# RPi_Extension_dac.net
KiCad netlist of a schematic drawn in EAGLE
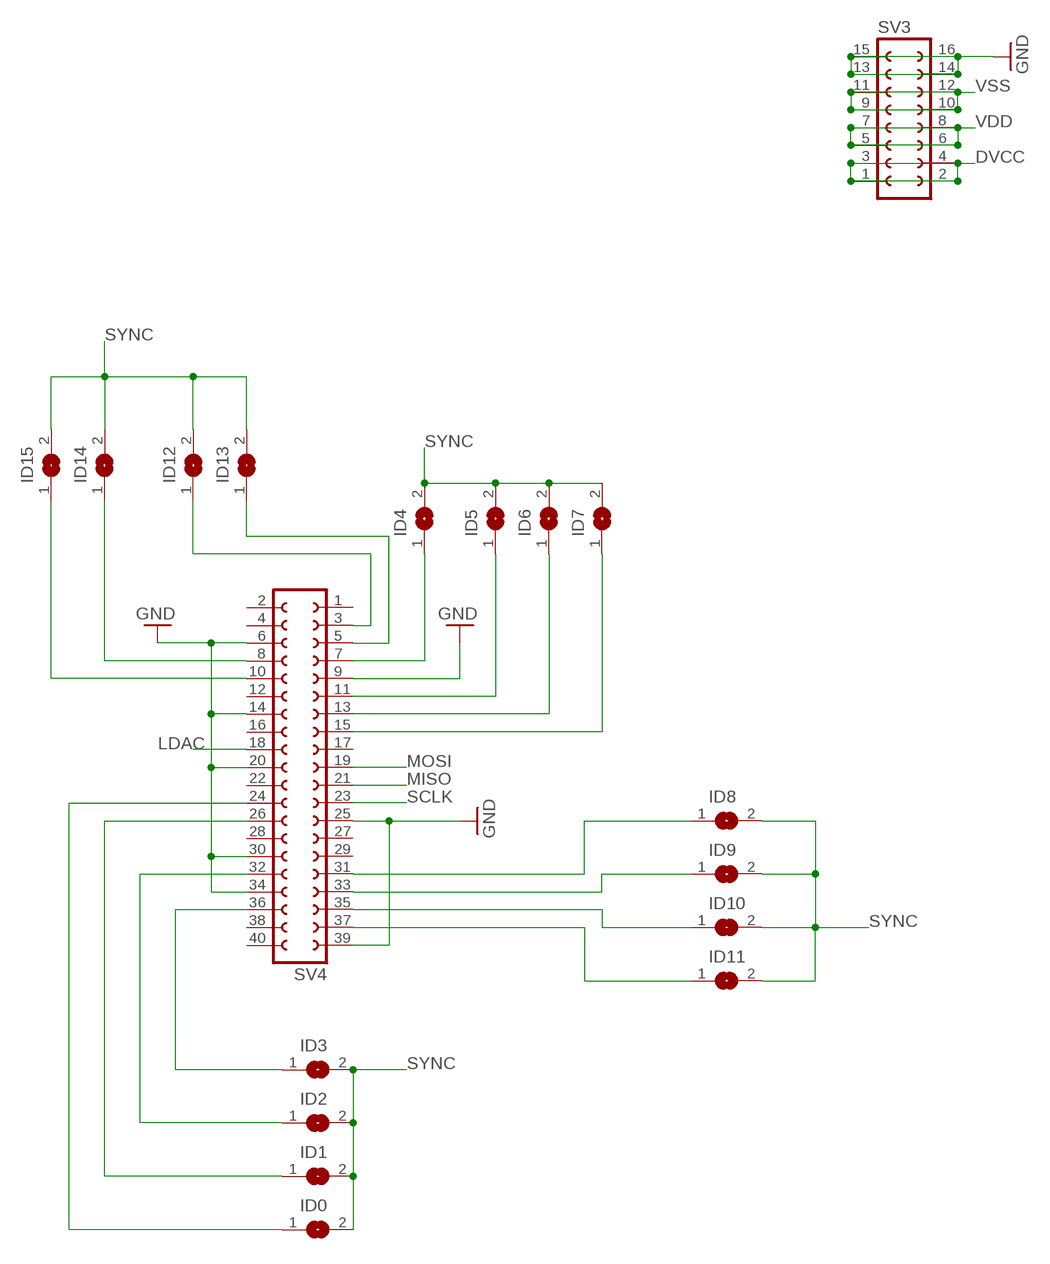
[diagram p0: schematic, sheet 1, part 1 of 2]
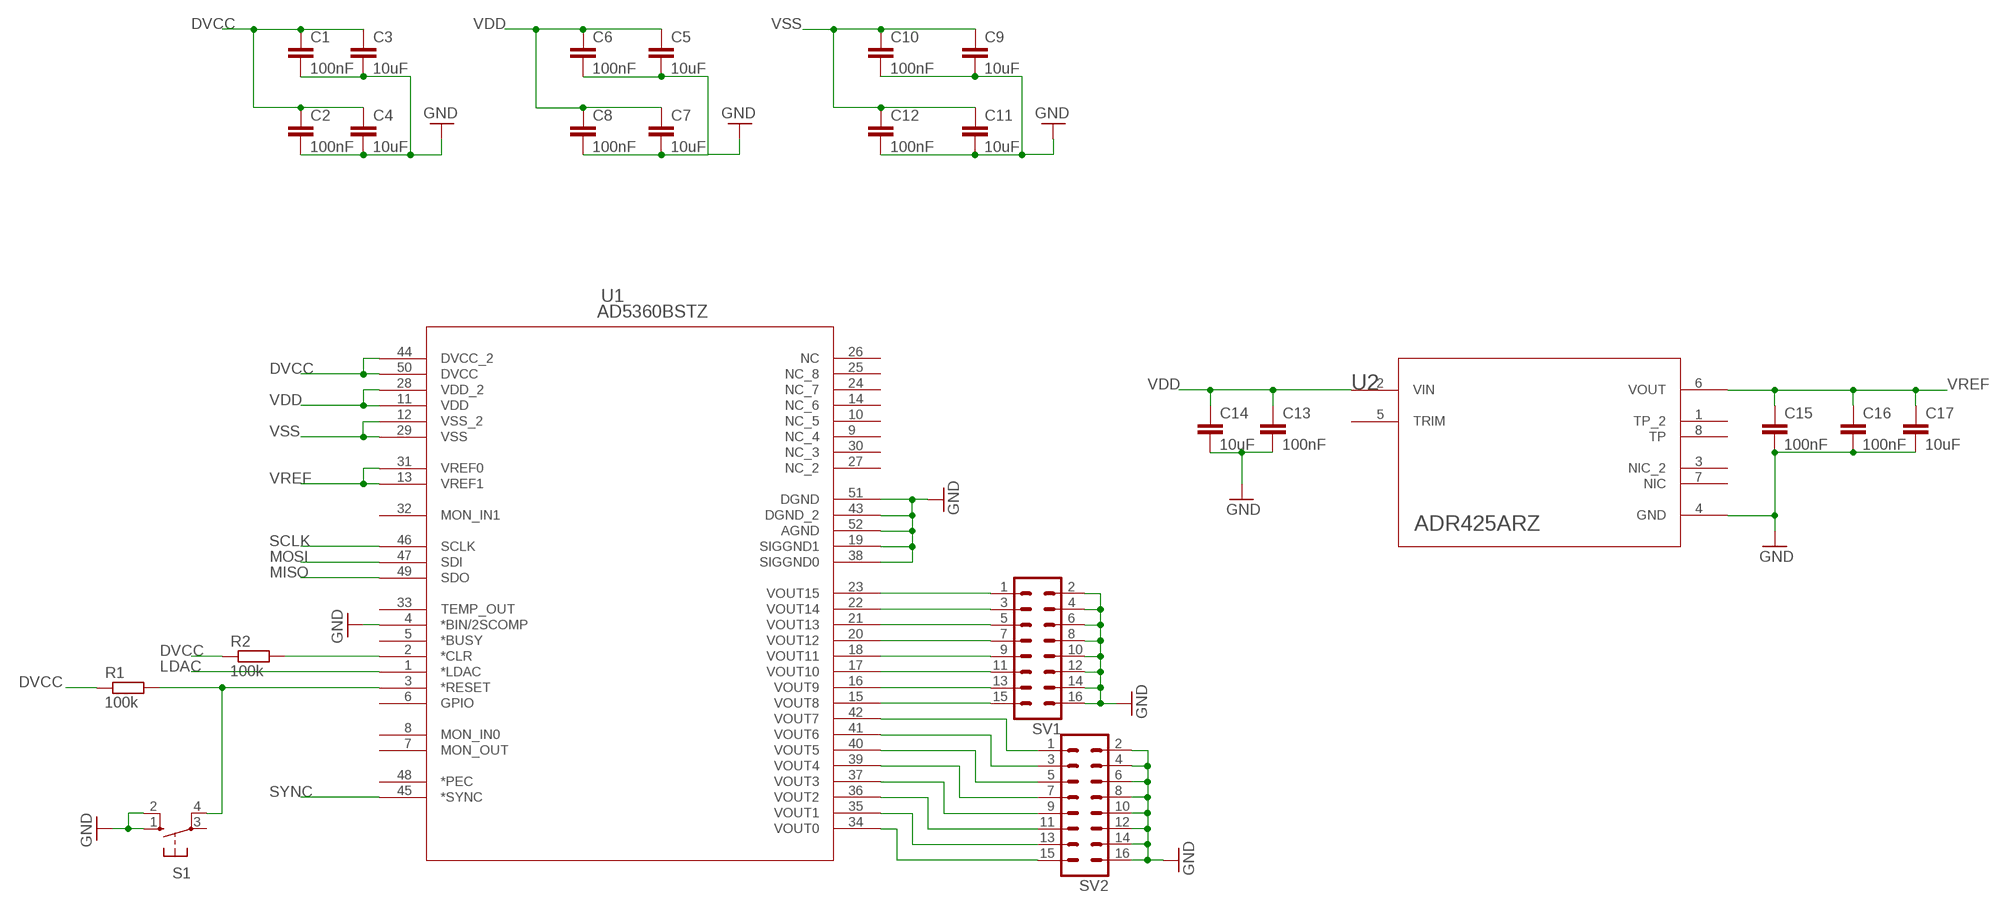
[diagram p1: schematic, sheet 1, part 2 of 2]

(export (version "E")
  (design (tool "Eeschema 10.0.6"))
  (components
    (comp (ref "C1")
      (value "100nF")
      (footprint "eagle-import:C0603")
      (libsource (lib "eagle-import") (part "C-EUC0603"))
    )
    (comp (ref "C2")
      (value "100nF")
      (footprint "eagle-import:C0603")
      (libsource (lib "eagle-import") (part "C-EUC0603"))
    )
    (comp (ref "C3")
      (value "10uF")
      (footprint "eagle-import:C1206")
      (libsource (lib "eagle-import") (part "C-EUC1206"))
    )
    (comp (ref "C4")
      (value "10uF")
      (footprint "eagle-import:C1206")
      (libsource (lib "eagle-import") (part "C-EUC1206"))
    )
    (comp (ref "C5")
      (value "10uF")
      (footprint "eagle-import:C1206")
      (libsource (lib "eagle-import") (part "C-EUC1206"))
    )
    (comp (ref "C6")
      (value "100nF")
      (footprint "eagle-import:C0603")
      (libsource (lib "eagle-import") (part "C-EUC0603"))
    )
    (comp (ref "C7")
      (value "10uF")
      (footprint "eagle-import:C1206")
      (libsource (lib "eagle-import") (part "C-EUC1206"))
    )
    (comp (ref "C8")
      (value "100nF")
      (footprint "eagle-import:C0603")
      (libsource (lib "eagle-import") (part "C-EUC0603"))
    )
    (comp (ref "C9")
      (value "10uF")
      (footprint "eagle-import:C1206")
      (libsource (lib "eagle-import") (part "C-EUC1206"))
    )
    (comp (ref "C10")
      (value "100nF")
      (footprint "eagle-import:C0603")
      (libsource (lib "eagle-import") (part "C-EUC0603"))
    )
    (comp (ref "C11")
      (value "10uF")
      (footprint "eagle-import:C1206")
      (libsource (lib "eagle-import") (part "C-EUC1206"))
    )
    (comp (ref "C12")
      (value "100nF")
      (footprint "eagle-import:C0603")
      (libsource (lib "eagle-import") (part "C-EUC0603"))
    )
    (comp (ref "C13")
      (value "100nF")
      (footprint "eagle-import:C0603")
      (libsource (lib "eagle-import") (part "C-EUC0603"))
    )
    (comp (ref "C14")
      (value "10uF")
      (footprint "eagle-import:C1206")
      (libsource (lib "eagle-import") (part "C-EUC1206"))
    )
    (comp (ref "C15")
      (value "100nF")
      (footprint "eagle-import:C0603")
      (libsource (lib "eagle-import") (part "C-EUC0603"))
    )
    (comp (ref "C16")
      (value "100nF")
      (footprint "eagle-import:C0603")
      (libsource (lib "eagle-import") (part "C-EUC0603"))
    )
    (comp (ref "C17")
      (value "10uF")
      (footprint "eagle-import:C1206")
      (libsource (lib "eagle-import") (part "C-EUC1206"))
    )
    (comp (ref "ID0") (value "SJ") (footprint "eagle-import:SJ") (libsource (lib "eagle-import") (part "SJ")))
    (comp (ref "ID1") (value "SJ") (footprint "eagle-import:SJ") (libsource (lib "eagle-import") (part "SJ")))
    (comp (ref "ID2") (value "SJ") (footprint "eagle-import:SJ") (libsource (lib "eagle-import") (part "SJ")))
    (comp (ref "ID3") (value "SJ") (footprint "eagle-import:SJ") (libsource (lib "eagle-import") (part "SJ")))
    (comp (ref "ID4") (value "SJ") (footprint "eagle-import:SJ") (libsource (lib "eagle-import") (part "SJ")))
    (comp (ref "ID5") (value "SJ") (footprint "eagle-import:SJ") (libsource (lib "eagle-import") (part "SJ")))
    (comp (ref "ID6") (value "SJ") (footprint "eagle-import:SJ") (libsource (lib "eagle-import") (part "SJ")))
    (comp (ref "ID7") (value "SJ") (footprint "eagle-import:SJ") (libsource (lib "eagle-import") (part "SJ")))
    (comp (ref "ID8") (value "SJ") (footprint "eagle-import:SJ") (libsource (lib "eagle-import") (part "SJ")))
    (comp (ref "ID9") (value "SJ") (footprint "eagle-import:SJ") (libsource (lib "eagle-import") (part "SJ")))
    (comp (ref "ID10")
      (value "SJ")
      (footprint "eagle-import:SJ")
      (libsource (lib "eagle-import") (part "SJ"))
    )
    (comp (ref "ID11")
      (value "SJ")
      (footprint "eagle-import:SJ")
      (libsource (lib "eagle-import") (part "SJ"))
    )
    (comp (ref "ID12")
      (value "SJ")
      (footprint "eagle-import:SJ")
      (libsource (lib "eagle-import") (part "SJ"))
    )
    (comp (ref "ID13")
      (value "SJ")
      (footprint "eagle-import:SJ")
      (libsource (lib "eagle-import") (part "SJ"))
    )
    (comp (ref "ID14")
      (value "SJ")
      (footprint "eagle-import:SJ")
      (libsource (lib "eagle-import") (part "SJ"))
    )
    (comp (ref "ID15")
      (value "SJ")
      (footprint "eagle-import:SJ")
      (libsource (lib "eagle-import") (part "SJ"))
    )
    (comp (ref "R1")
      (value "100k")
      (footprint "eagle-import:R0603")
      (libsource (lib "eagle-import") (part "R-EU_R0603"))
    )
    (comp (ref "R2")
      (value "100k")
      (footprint "eagle-import:R0603")
      (libsource (lib "eagle-import") (part "R-EU_R0603"))
    )
    (comp (ref "S1")
      (value "10-XX")
      (footprint "eagle-import:B3F-10XX")
      (fields (field (name "MPN") "B3F-1000"))
      (libsource (lib "eagle-import") (part "10-XX"))
    )
    (comp (ref "SV1")
      (value "MA08-2W")
      (footprint "eagle-import:MA08-2W")
      (libsource (lib "eagle-import") (part "MA08-2W"))
    )
    (comp (ref "SV2")
      (value "MA08-2W")
      (footprint "eagle-import:MA08-2W")
      (libsource (lib "eagle-import") (part "MA08-2W"))
    )
    (comp (ref "SV3")
      (value "FE08-2")
      (footprint "eagle-import:FE08-2")
      (libsource (lib "eagle-import") (part "FE08-2"))
    )
    (comp (ref "SV4")
      (value "FE20-2")
      (footprint "eagle-import:FE20-2")
      (libsource (lib "eagle-import") (part "FE20-2"))
    )
    (comp (ref "U1")
      (value "AD5360BSTZ")
      (footprint "eagle-import:ST_52")
      (libsource (lib "eagle-import") (part "AD5360BSTZ"))
    )
    (comp (ref "U2")
      (value "ADR425ARZ")
      (footprint "eagle-import:R_8")
      (fields (field (name "MANUFACTURER_PART_NUMBER") "ADR423ARZ"))
      (libsource (lib "eagle-import") (part "ADR423ARZ"))
    )
  )
  (nets
    (net (code "1") (name "/DVCC") (class "Default")
      (node (ref "C1") (pin "1") (pinfunction "1_1") (pintype "passive"))
      (node (ref "C2") (pin "1") (pinfunction "1_1") (pintype "passive"))
      (node (ref "C3") (pin "1") (pinfunction "1_1") (pintype "passive"))
      (node (ref "C4") (pin "1") (pinfunction "1_1") (pintype "passive"))
      (node (ref "R1") (pin "1") (pinfunction "1_1") (pintype "passive"))
      (node (ref "R2") (pin "1") (pinfunction "1_1") (pintype "passive"))
      (node (ref "SV3") (pin "1") (pinfunction "1_1") (pintype "passive"))
      (node (ref "SV3") (pin "2") (pinfunction "2_2") (pintype "passive"))
      (node (ref "SV3") (pin "3") (pinfunction "3_3") (pintype "passive"))
      (node (ref "SV3") (pin "4") (pinfunction "4_4") (pintype "passive"))
      (node (ref "U1") (pin "44") (pinfunction "DVCC_2_44") (pintype "passive"))
      (node (ref "U1") (pin "50") (pinfunction "DVCC_50") (pintype "passive"))
    )
    (net (code "2") (name "/LDAC") (class "Default")
      (node (ref "SV4") (pin "18") (pinfunction "18_18") (pintype "passive"))
      (node (ref "U1") (pin "1") (pinfunction "*LDAC_1") (pintype "passive"))
    )
    (net (code "3") (name "/MISO") (class "Default")
      (node (ref "SV4") (pin "21") (pinfunction "21_21") (pintype "passive"))
      (node (ref "U1") (pin "49") (pinfunction "SDO_49") (pintype "passive"))
    )
    (net (code "4") (name "/MOSI") (class "Default")
      (node (ref "SV4") (pin "19") (pinfunction "19_19") (pintype "passive"))
      (node (ref "U1") (pin "47") (pinfunction "SDI_47") (pintype "passive"))
    )
    (net (code "5") (name "/SCLK") (class "Default")
      (node (ref "SV4") (pin "23") (pinfunction "23_23") (pintype "passive"))
      (node (ref "U1") (pin "46") (pinfunction "SCLK_46") (pintype "passive"))
    )
    (net (code "6") (name "/SYNC") (class "Default")
      (node (ref "ID0") (pin "2") (pinfunction "2_2") (pintype "passive"))
      (node (ref "ID1") (pin "2") (pinfunction "2_2") (pintype "passive"))
      (node (ref "ID10") (pin "2") (pinfunction "2_2") (pintype "passive"))
      (node (ref "ID11") (pin "2") (pinfunction "2_2") (pintype "passive"))
      (node (ref "ID12") (pin "2") (pinfunction "2_2") (pintype "passive"))
      (node (ref "ID13") (pin "2") (pinfunction "2_2") (pintype "passive"))
      (node (ref "ID14") (pin "2") (pinfunction "2_2") (pintype "passive"))
      (node (ref "ID15") (pin "2") (pinfunction "2_2") (pintype "passive"))
      (node (ref "ID2") (pin "2") (pinfunction "2_2") (pintype "passive"))
      (node (ref "ID3") (pin "2") (pinfunction "2_2") (pintype "passive"))
      (node (ref "ID4") (pin "2") (pinfunction "2_2") (pintype "passive"))
      (node (ref "ID5") (pin "2") (pinfunction "2_2") (pintype "passive"))
      (node (ref "ID6") (pin "2") (pinfunction "2_2") (pintype "passive"))
      (node (ref "ID7") (pin "2") (pinfunction "2_2") (pintype "passive"))
      (node (ref "ID8") (pin "2") (pinfunction "2_2") (pintype "passive"))
      (node (ref "ID9") (pin "2") (pinfunction "2_2") (pintype "passive"))
      (node (ref "U1") (pin "45") (pinfunction "*SYNC_45") (pintype "passive"))
    )
    (net (code "7") (name "/VDD") (class "Default")
      (node (ref "C13") (pin "1") (pinfunction "1_1") (pintype "passive"))
      (node (ref "C14") (pin "1") (pinfunction "1_1") (pintype "passive"))
      (node (ref "C5") (pin "1") (pinfunction "1_1") (pintype "passive"))
      (node (ref "C6") (pin "1") (pinfunction "1_1") (pintype "passive"))
      (node (ref "C7") (pin "1") (pinfunction "1_1") (pintype "passive"))
      (node (ref "C8") (pin "1") (pinfunction "1_1") (pintype "passive"))
      (node (ref "SV3") (pin "5") (pinfunction "5_5") (pintype "passive"))
      (node (ref "SV3") (pin "6") (pinfunction "6_6") (pintype "passive"))
      (node (ref "SV3") (pin "7") (pinfunction "7_7") (pintype "passive"))
      (node (ref "SV3") (pin "8") (pinfunction "8_8") (pintype "passive"))
      (node (ref "U1") (pin "11") (pinfunction "VDD_11") (pintype "passive"))
      (node (ref "U1") (pin "28") (pinfunction "VDD_2_28") (pintype "passive"))
      (node (ref "U2") (pin "2") (pinfunction "VIN_2") (pintype "passive"))
    )
    (net (code "8") (name "/VREF") (class "Default")
      (node (ref "C15") (pin "1") (pinfunction "1_1") (pintype "passive"))
      (node (ref "C16") (pin "1") (pinfunction "1_1") (pintype "passive"))
      (node (ref "C17") (pin "1") (pinfunction "1_1") (pintype "passive"))
      (node (ref "U1") (pin "13") (pinfunction "VREF1_13") (pintype "passive"))
      (node (ref "U1") (pin "31") (pinfunction "VREF0_31") (pintype "passive"))
      (node (ref "U2") (pin "6") (pinfunction "VOUT_6") (pintype "passive"))
    )
    (net (code "9") (name "/VSS") (class "Default")
      (node (ref "C10") (pin "1") (pinfunction "1_1") (pintype "passive"))
      (node (ref "C11") (pin "1") (pinfunction "1_1") (pintype "passive"))
      (node (ref "C12") (pin "1") (pinfunction "1_1") (pintype "passive"))
      (node (ref "C9") (pin "1") (pinfunction "1_1") (pintype "passive"))
      (node (ref "SV3") (pin "10") (pinfunction "10_10") (pintype "passive"))
      (node (ref "SV3") (pin "11") (pinfunction "11_11") (pintype "passive"))
      (node (ref "SV3") (pin "12") (pinfunction "12_12") (pintype "passive"))
      (node (ref "SV3") (pin "9") (pinfunction "9_9") (pintype "passive"))
      (node (ref "U1") (pin "12") (pinfunction "VSS_2_12") (pintype "passive"))
      (node (ref "U1") (pin "29") (pinfunction "VSS_29") (pintype "passive"))
    )
    (net (code "10") (name "GND") (class "Default")
      (node (ref "C1") (pin "2") (pinfunction "2_2") (pintype "passive"))
      (node (ref "C10") (pin "2") (pinfunction "2_2") (pintype "passive"))
      (node (ref "C11") (pin "2") (pinfunction "2_2") (pintype "passive"))
      (node (ref "C12") (pin "2") (pinfunction "2_2") (pintype "passive"))
      (node (ref "C13") (pin "2") (pinfunction "2_2") (pintype "passive"))
      (node (ref "C14") (pin "2") (pinfunction "2_2") (pintype "passive"))
      (node (ref "C15") (pin "2") (pinfunction "2_2") (pintype "passive"))
      (node (ref "C16") (pin "2") (pinfunction "2_2") (pintype "passive"))
      (node (ref "C17") (pin "2") (pinfunction "2_2") (pintype "passive"))
      (node (ref "C2") (pin "2") (pinfunction "2_2") (pintype "passive"))
      (node (ref "C3") (pin "2") (pinfunction "2_2") (pintype "passive"))
      (node (ref "C4") (pin "2") (pinfunction "2_2") (pintype "passive"))
      (node (ref "C5") (pin "2") (pinfunction "2_2") (pintype "passive"))
      (node (ref "C6") (pin "2") (pinfunction "2_2") (pintype "passive"))
      (node (ref "C7") (pin "2") (pinfunction "2_2") (pintype "passive"))
      (node (ref "C8") (pin "2") (pinfunction "2_2") (pintype "passive"))
      (node (ref "C9") (pin "2") (pinfunction "2_2") (pintype "passive"))
      (node (ref "S1") (pin "1") (pinfunction "S_1") (pintype "passive"))
      (node (ref "S1") (pin "2") (pinfunction "S1_2") (pintype "passive"))
      (node (ref "SV1") (pin "10") (pinfunction "10_10") (pintype "passive"))
      (node (ref "SV1") (pin "12") (pinfunction "12_12") (pintype "passive"))
      (node (ref "SV1") (pin "14") (pinfunction "14_14") (pintype "passive"))
      (node (ref "SV1") (pin "16") (pinfunction "16_16") (pintype "passive"))
      (node (ref "SV1") (pin "2") (pinfunction "2_2") (pintype "passive"))
      (node (ref "SV1") (pin "4") (pinfunction "4_4") (pintype "passive"))
      (node (ref "SV1") (pin "6") (pinfunction "6_6") (pintype "passive"))
      (node (ref "SV1") (pin "8") (pinfunction "8_8") (pintype "passive"))
      (node (ref "SV2") (pin "10") (pinfunction "10_10") (pintype "passive"))
      (node (ref "SV2") (pin "12") (pinfunction "12_12") (pintype "passive"))
      (node (ref "SV2") (pin "14") (pinfunction "14_14") (pintype "passive"))
      (node (ref "SV2") (pin "16") (pinfunction "16_16") (pintype "passive"))
      (node (ref "SV2") (pin "2") (pinfunction "2_2") (pintype "passive"))
      (node (ref "SV2") (pin "4") (pinfunction "4_4") (pintype "passive"))
      (node (ref "SV2") (pin "6") (pinfunction "6_6") (pintype "passive"))
      (node (ref "SV2") (pin "8") (pinfunction "8_8") (pintype "passive"))
      (node (ref "SV3") (pin "13") (pinfunction "13_13") (pintype "passive"))
      (node (ref "SV3") (pin "14") (pinfunction "14_14") (pintype "passive"))
      (node (ref "SV3") (pin "15") (pinfunction "15_15") (pintype "passive"))
      (node (ref "SV3") (pin "16") (pinfunction "16_16") (pintype "passive"))
      (node (ref "SV4") (pin "14") (pinfunction "14_14") (pintype "passive"))
      (node (ref "SV4") (pin "20") (pinfunction "20_20") (pintype "passive"))
      (node (ref "SV4") (pin "25") (pinfunction "25_25") (pintype "passive"))
      (node (ref "SV4") (pin "30") (pinfunction "30_30") (pintype "passive"))
      (node (ref "SV4") (pin "34") (pinfunction "34_34") (pintype "passive"))
      (node (ref "SV4") (pin "39") (pinfunction "39_39") (pintype "passive"))
      (node (ref "SV4") (pin "6") (pinfunction "6_6") (pintype "passive"))
      (node (ref "SV4") (pin "9") (pinfunction "9_9") (pintype "passive"))
      (node (ref "U1") (pin "19") (pinfunction "SIGGND1_19") (pintype "passive"))
      (node (ref "U1") (pin "38") (pinfunction "SIGGND0_38") (pintype "passive"))
      (node (ref "U1") (pin "4") (pinfunction "*BIN/2SCOMP_4") (pintype "passive"))
      (node (ref "U1") (pin "43") (pinfunction "DGND_2_43") (pintype "passive"))
      (node (ref "U1") (pin "51") (pinfunction "DGND_51") (pintype "passive"))
      (node (ref "U1") (pin "52") (pinfunction "AGND_52") (pintype "passive"))
      (node (ref "U2") (pin "4") (pinfunction "GND_4") (pintype "passive"))
    )
    (net (code "11") (name "Net-(ID0-Pad1)") (class "Default")
      (node (ref "ID0") (pin "1") (pinfunction "1_1") (pintype "passive"))
      (node (ref "SV4") (pin "24") (pinfunction "24_24") (pintype "passive"))
    )
    (net (code "12") (name "Net-(ID1-Pad1)") (class "Default")
      (node (ref "ID1") (pin "1") (pinfunction "1_1") (pintype "passive"))
      (node (ref "SV4") (pin "26") (pinfunction "26_26") (pintype "passive"))
    )
    (net (code "13") (name "Net-(ID2-Pad1)") (class "Default")
      (node (ref "ID2") (pin "1") (pinfunction "1_1") (pintype "passive"))
      (node (ref "SV4") (pin "32") (pinfunction "32_32") (pintype "passive"))
    )
    (net (code "14") (name "Net-(ID3-Pad1)") (class "Default")
      (node (ref "ID3") (pin "1") (pinfunction "1_1") (pintype "passive"))
      (node (ref "SV4") (pin "36") (pinfunction "36_36") (pintype "passive"))
    )
    (net (code "15") (name "Net-(ID4-Pad1)") (class "Default")
      (node (ref "ID4") (pin "1") (pinfunction "1_1") (pintype "passive"))
      (node (ref "SV4") (pin "7") (pinfunction "7_7") (pintype "passive"))
    )
    (net (code "16") (name "Net-(ID5-Pad1)") (class "Default")
      (node (ref "ID5") (pin "1") (pinfunction "1_1") (pintype "passive"))
      (node (ref "SV4") (pin "11") (pinfunction "11_11") (pintype "passive"))
    )
    (net (code "17") (name "Net-(ID6-Pad1)") (class "Default")
      (node (ref "ID6") (pin "1") (pinfunction "1_1") (pintype "passive"))
      (node (ref "SV4") (pin "13") (pinfunction "13_13") (pintype "passive"))
    )
    (net (code "18") (name "Net-(ID7-Pad1)") (class "Default")
      (node (ref "ID7") (pin "1") (pinfunction "1_1") (pintype "passive"))
      (node (ref "SV4") (pin "15") (pinfunction "15_15") (pintype "passive"))
    )
    (net (code "19") (name "Net-(ID8-Pad1)") (class "Default")
      (node (ref "ID8") (pin "1") (pinfunction "1_1") (pintype "passive"))
      (node (ref "SV4") (pin "31") (pinfunction "31_31") (pintype "passive"))
    )
    (net (code "20") (name "Net-(ID9-Pad1)") (class "Default")
      (node (ref "ID9") (pin "1") (pinfunction "1_1") (pintype "passive"))
      (node (ref "SV4") (pin "33") (pinfunction "33_33") (pintype "passive"))
    )
    (net (code "21") (name "Net-(ID10-Pad1)") (class "Default")
      (node (ref "ID10") (pin "1") (pinfunction "1_1") (pintype "passive"))
      (node (ref "SV4") (pin "35") (pinfunction "35_35") (pintype "passive"))
    )
    (net (code "22") (name "Net-(ID11-Pad1)") (class "Default")
      (node (ref "ID11") (pin "1") (pinfunction "1_1") (pintype "passive"))
      (node (ref "SV4") (pin "37") (pinfunction "37_37") (pintype "passive"))
    )
    (net (code "23") (name "Net-(ID12-Pad1)") (class "Default")
      (node (ref "ID12") (pin "1") (pinfunction "1_1") (pintype "passive"))
      (node (ref "SV4") (pin "3") (pinfunction "3_3") (pintype "passive"))
    )
    (net (code "24") (name "Net-(ID13-Pad1)") (class "Default")
      (node (ref "ID13") (pin "1") (pinfunction "1_1") (pintype "passive"))
      (node (ref "SV4") (pin "5") (pinfunction "5_5") (pintype "passive"))
    )
    (net (code "25") (name "Net-(ID14-Pad1)") (class "Default")
      (node (ref "ID14") (pin "1") (pinfunction "1_1") (pintype "passive"))
      (node (ref "SV4") (pin "8") (pinfunction "8_8") (pintype "passive"))
    )
    (net (code "26") (name "Net-(ID15-Pad1)") (class "Default")
      (node (ref "ID15") (pin "1") (pinfunction "1_1") (pintype "passive"))
      (node (ref "SV4") (pin "10") (pinfunction "10_10") (pintype "passive"))
    )
    (net (code "27") (name "Net-(S1-P1)") (class "Default")
      (node (ref "R1") (pin "2") (pinfunction "2_2") (pintype "passive"))
      (node (ref "S1") (pin "4") (pinfunction "P1_4") (pintype "passive"))
      (node (ref "U1") (pin "3") (pinfunction "*RESET_3") (pintype "passive"))
    )
    (net (code "28") (name "Net-(U1-*CLR)") (class "Default")
      (node (ref "R2") (pin "2") (pinfunction "2_2") (pintype "passive"))
      (node (ref "U1") (pin "2") (pinfunction "*CLR_2") (pintype "passive"))
    )
    (net (code "29") (name "Net-(U1-VOUT0)") (class "Default")
      (node (ref "SV2") (pin "15") (pinfunction "15_15") (pintype "passive"))
      (node (ref "U1") (pin "34") (pinfunction "VOUT0_34") (pintype "passive"))
    )
    (net (code "30") (name "Net-(U1-VOUT1)") (class "Default")
      (node (ref "SV2") (pin "13") (pinfunction "13_13") (pintype "passive"))
      (node (ref "U1") (pin "35") (pinfunction "VOUT1_35") (pintype "passive"))
    )
    (net (code "31") (name "Net-(U1-VOUT2)") (class "Default")
      (node (ref "SV2") (pin "11") (pinfunction "11_11") (pintype "passive"))
      (node (ref "U1") (pin "36") (pinfunction "VOUT2_36") (pintype "passive"))
    )
    (net (code "32") (name "Net-(U1-VOUT3)") (class "Default")
      (node (ref "SV2") (pin "9") (pinfunction "9_9") (pintype "passive"))
      (node (ref "U1") (pin "37") (pinfunction "VOUT3_37") (pintype "passive"))
    )
    (net (code "33") (name "Net-(U1-VOUT4)") (class "Default")
      (node (ref "SV2") (pin "7") (pinfunction "7_7") (pintype "passive"))
      (node (ref "U1") (pin "39") (pinfunction "VOUT4_39") (pintype "passive"))
    )
    (net (code "34") (name "Net-(U1-VOUT5)") (class "Default")
      (node (ref "SV2") (pin "5") (pinfunction "5_5") (pintype "passive"))
      (node (ref "U1") (pin "40") (pinfunction "VOUT5_40") (pintype "passive"))
    )
    (net (code "35") (name "Net-(U1-VOUT6)") (class "Default")
      (node (ref "SV2") (pin "3") (pinfunction "3_3") (pintype "passive"))
      (node (ref "U1") (pin "41") (pinfunction "VOUT6_41") (pintype "passive"))
    )
    (net (code "36") (name "Net-(U1-VOUT7)") (class "Default")
      (node (ref "SV2") (pin "1") (pinfunction "1_1") (pintype "passive"))
      (node (ref "U1") (pin "42") (pinfunction "VOUT7_42") (pintype "passive"))
    )
    (net (code "37") (name "Net-(U1-VOUT8)") (class "Default")
      (node (ref "SV1") (pin "15") (pinfunction "15_15") (pintype "passive"))
      (node (ref "U1") (pin "15") (pinfunction "VOUT8_15") (pintype "passive"))
    )
    (net (code "38") (name "Net-(U1-VOUT9)") (class "Default")
      (node (ref "SV1") (pin "13") (pinfunction "13_13") (pintype "passive"))
      (node (ref "U1") (pin "16") (pinfunction "VOUT9_16") (pintype "passive"))
    )
    (net (code "39") (name "Net-(U1-VOUT10)") (class "Default")
      (node (ref "SV1") (pin "11") (pinfunction "11_11") (pintype "passive"))
      (node (ref "U1") (pin "17") (pinfunction "VOUT10_17") (pintype "passive"))
    )
    (net (code "40") (name "Net-(U1-VOUT11)") (class "Default")
      (node (ref "SV1") (pin "9") (pinfunction "9_9") (pintype "passive"))
      (node (ref "U1") (pin "18") (pinfunction "VOUT11_18") (pintype "passive"))
    )
    (net (code "41") (name "Net-(U1-VOUT12)") (class "Default")
      (node (ref "SV1") (pin "7") (pinfunction "7_7") (pintype "passive"))
      (node (ref "U1") (pin "20") (pinfunction "VOUT12_20") (pintype "passive"))
    )
    (net (code "42") (name "Net-(U1-VOUT13)") (class "Default")
      (node (ref "SV1") (pin "5") (pinfunction "5_5") (pintype "passive"))
      (node (ref "U1") (pin "21") (pinfunction "VOUT13_21") (pintype "passive"))
    )
    (net (code "43") (name "Net-(U1-VOUT14)") (class "Default")
      (node (ref "SV1") (pin "3") (pinfunction "3_3") (pintype "passive"))
      (node (ref "U1") (pin "22") (pinfunction "VOUT14_22") (pintype "passive"))
    )
    (net (code "44") (name "Net-(U1-VOUT15)") (class "Default")
      (node (ref "SV1") (pin "1") (pinfunction "1_1") (pintype "passive"))
      (node (ref "U1") (pin "23") (pinfunction "VOUT15_23") (pintype "passive"))
    )
    (net (code "45") (name "unconnected-(S1-P-Pad3)") (class "Default")
      (node (ref "S1") (pin "3") (pinfunction "P_3") (pintype "passive"))
    )
    (net (code "46") (name "unconnected-(SV4-Pad1)") (class "Default")
      (node (ref "SV4") (pin "1") (pinfunction "1_1") (pintype "passive"))
    )
    (net (code "47") (name "unconnected-(SV4-Pad2)") (class "Default")
      (node (ref "SV4") (pin "2") (pinfunction "2_2") (pintype "passive"))
    )
    (net (code "48") (name "unconnected-(SV4-Pad4)") (class "Default")
      (node (ref "SV4") (pin "4") (pinfunction "4_4") (pintype "passive"))
    )
    (net (code "49") (name "unconnected-(SV4-Pad12)") (class "Default")
      (node (ref "SV4") (pin "12") (pinfunction "12_12") (pintype "passive"))
    )
    (net (code "50") (name "unconnected-(SV4-Pad16)") (class "Default")
      (node (ref "SV4") (pin "16") (pinfunction "16_16") (pintype "passive"))
    )
    (net (code "51") (name "unconnected-(SV4-Pad17)") (class "Default")
      (node (ref "SV4") (pin "17") (pinfunction "17_17") (pintype "passive"))
    )
    (net (code "52") (name "unconnected-(SV4-Pad22)") (class "Default")
      (node (ref "SV4") (pin "22") (pinfunction "22_22") (pintype "passive"))
    )
    (net (code "53") (name "unconnected-(SV4-Pad27)") (class "Default")
      (node (ref "SV4") (pin "27") (pinfunction "27_27") (pintype "passive"))
    )
    (net (code "54") (name "unconnected-(SV4-Pad28)") (class "Default")
      (node (ref "SV4") (pin "28") (pinfunction "28_28") (pintype "passive"))
    )
    (net (code "55") (name "unconnected-(SV4-Pad29)") (class "Default")
      (node (ref "SV4") (pin "29") (pinfunction "29_29") (pintype "passive"))
    )
    (net (code "56") (name "unconnected-(SV4-Pad38)") (class "Default")
      (node (ref "SV4") (pin "38") (pinfunction "38_38") (pintype "passive"))
    )
    (net (code "57") (name "unconnected-(SV4-Pad40)") (class "Default")
      (node (ref "SV4") (pin "40") (pinfunction "40_40") (pintype "passive"))
    )
    (net (code "58") (name "unconnected-(U1-*BUSY-Pad5)") (class "Default")
      (node (ref "U1") (pin "5") (pinfunction "*BUSY_5") (pintype "passive"))
    )
    (net (code "59") (name "unconnected-(U1-*PEC-Pad48)") (class "Default")
      (node (ref "U1") (pin "48") (pinfunction "*PEC_48") (pintype "passive"))
    )
    (net (code "60") (name "unconnected-(U1-GPIO-Pad6)") (class "Default")
      (node (ref "U1") (pin "6") (pinfunction "GPIO_6") (pintype "passive"))
    )
    (net (code "61") (name "unconnected-(U1-MON_IN0-Pad8)") (class "Default")
      (node (ref "U1") (pin "8") (pinfunction "MON_IN0_8") (pintype "passive"))
    )
    (net (code "62") (name "unconnected-(U1-MON_IN1-Pad32)") (class "Default")
      (node (ref "U1") (pin "32") (pinfunction "MON_IN1_32") (pintype "passive"))
    )
    (net (code "63") (name "unconnected-(U1-MON_OUT-Pad7)") (class "Default")
      (node (ref "U1") (pin "7") (pinfunction "MON_OUT_7") (pintype "passive"))
    )
    (net (code "64") (name "unconnected-(U1-NC-Pad26)") (class "Default")
      (node (ref "U1") (pin "26") (pinfunction "NC_26") (pintype "passive"))
    )
    (net (code "65") (name "unconnected-(U1-NC_2-Pad27)") (class "Default")
      (node (ref "U1") (pin "27") (pinfunction "NC_2_27") (pintype "passive"))
    )
    (net (code "66") (name "unconnected-(U1-NC_3-Pad30)") (class "Default")
      (node (ref "U1") (pin "30") (pinfunction "NC_3_30") (pintype "passive"))
    )
    (net (code "67") (name "unconnected-(U1-NC_4-Pad9)") (class "Default")
      (node (ref "U1") (pin "9") (pinfunction "NC_4_9") (pintype "passive"))
    )
    (net (code "68") (name "unconnected-(U1-NC_5-Pad10)") (class "Default")
      (node (ref "U1") (pin "10") (pinfunction "NC_5_10") (pintype "passive"))
    )
    (net (code "69") (name "unconnected-(U1-NC_6-Pad14)") (class "Default")
      (node (ref "U1") (pin "14") (pinfunction "NC_6_14") (pintype "passive"))
    )
    (net (code "70") (name "unconnected-(U1-NC_7-Pad24)") (class "Default")
      (node (ref "U1") (pin "24") (pinfunction "NC_7_24") (pintype "passive"))
    )
    (net (code "71") (name "unconnected-(U1-NC_8-Pad25)") (class "Default")
      (node (ref "U1") (pin "25") (pinfunction "NC_8_25") (pintype "passive"))
    )
    (net (code "72") (name "unconnected-(U1-TEMP_OUT-Pad33)") (class "Default")
      (node (ref "U1") (pin "33") (pinfunction "TEMP_OUT_33") (pintype "passive"))
    )
    (net (code "73") (name "unconnected-(U2-NIC-Pad7)") (class "Default")
      (node (ref "U2") (pin "7") (pinfunction "NIC_7") (pintype "passive"))
    )
    (net (code "74") (name "unconnected-(U2-NIC_2-Pad3)") (class "Default")
      (node (ref "U2") (pin "3") (pinfunction "NIC_2_3") (pintype "passive"))
    )
    (net (code "75") (name "unconnected-(U2-TP-Pad8)") (class "Default")
      (node (ref "U2") (pin "8") (pinfunction "TP_8") (pintype "passive"))
    )
    (net (code "76") (name "unconnected-(U2-TP_2-Pad1)") (class "Default")
      (node (ref "U2") (pin "1") (pinfunction "TP_2_1") (pintype "passive"))
    )
    (net (code "77") (name "unconnected-(U2-TRIM-Pad5)") (class "Default")
      (node (ref "U2") (pin "5") (pinfunction "TRIM_5") (pintype "passive"))
    )
  )
)
